# RJ45-2.net
KiCad netlist of a schematic drawn in Altium Designer
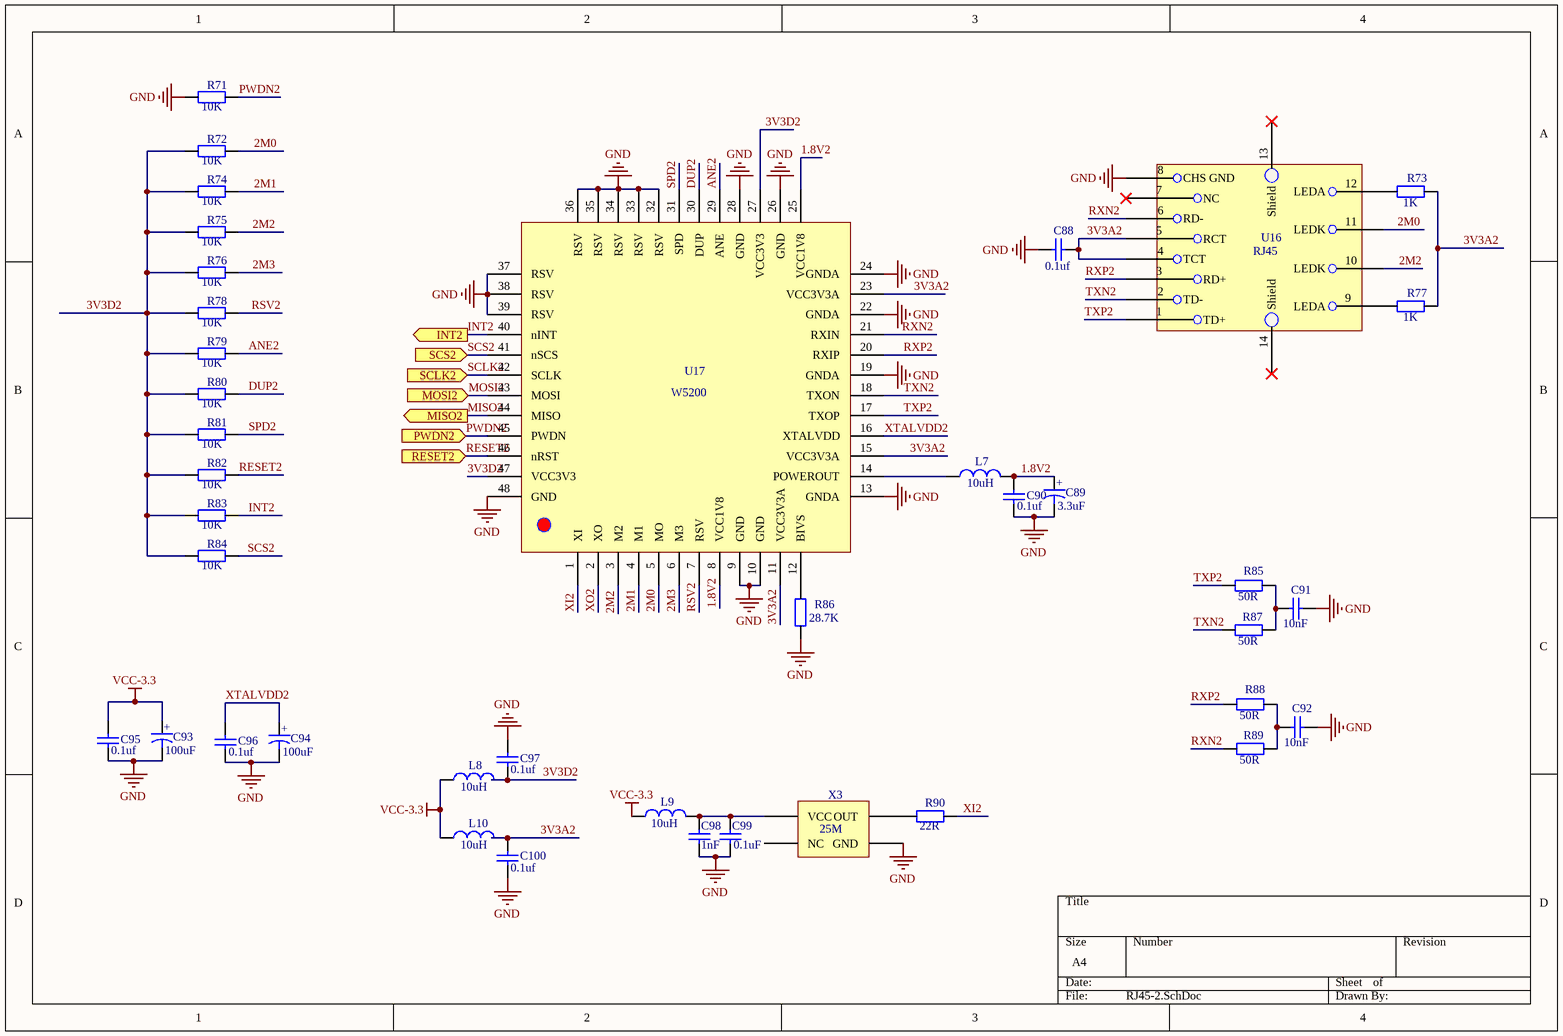
[diagram p0: RJ45-2.SchDoc]

(export (version "E")
  (design (tool "Eeschema 10.0.6"))
  (components
    (comp (ref "C88")
      (value "0.1uf")
      (footprint "0603")
      (fields (field (name "Comment") "Capacitor-0603"))
      (libsource (lib "原理图库") (part "Capacitor-0603"))
    )
    (comp (ref "C89")
      (value "3.3uF")
      (footprint "钽电容1206（A3216）")
      (fields (field (name "ALTIUM_UNNAMED_1") "+") (field (name "Comment") "电解电容"))
      (libsource (lib "原理图库") (part "电解电容"))
    )
    (comp (ref "C90")
      (value "0.1uf")
      (footprint "0603")
      (fields (field (name "Comment") "Capacitor-0603"))
      (libsource (lib "原理图库") (part "Capacitor-0603"))
    )
    (comp (ref "C91")
      (value "10nF")
      (footprint "0603")
      (fields (field (name "Comment") "Capacitor-0603"))
      (libsource (lib "原理图库") (part "Capacitor-0603"))
    )
    (comp (ref "C92")
      (value "10nF")
      (footprint "0603")
      (fields (field (name "Comment") "Capacitor-0603"))
      (libsource (lib "原理图库") (part "Capacitor-0603"))
    )
    (comp (ref "C93")
      (value "100uF")
      (footprint "钽电容1206（A3216）")
      (fields (field (name "ALTIUM_UNNAMED_1") "+") (field (name "Comment") "电解电容"))
      (libsource (lib "原理图库") (part "电解电容"))
    )
    (comp (ref "C94")
      (value "100uF")
      (footprint "钽电容1206（A3216）")
      (fields (field (name "ALTIUM_UNNAMED_1") "+") (field (name "Comment") "电解电容"))
      (libsource (lib "原理图库") (part "电解电容"))
    )
    (comp (ref "C95")
      (value "0.1uf")
      (footprint "0603")
      (fields (field (name "Comment") "Capacitor-0603"))
      (libsource (lib "原理图库") (part "Capacitor-0603"))
    )
    (comp (ref "C96")
      (value "0.1uf")
      (footprint "0603")
      (fields (field (name "Comment") "Capacitor-0603"))
      (libsource (lib "原理图库") (part "Capacitor-0603"))
    )
    (comp (ref "C97")
      (value "0.1uf")
      (footprint "0603")
      (fields (field (name "Comment") "Capacitor-0603"))
      (libsource (lib "原理图库") (part "Capacitor-0603"))
    )
    (comp (ref "C98")
      (value "1nF")
      (footprint "0603")
      (fields (field (name "Comment") "Capacitor-0603"))
      (libsource (lib "原理图库") (part "Capacitor-0603"))
    )
    (comp (ref "C99")
      (value "0.1uF")
      (footprint "0603")
      (fields (field (name "Comment") "Capacitor-0603"))
      (libsource (lib "原理图库") (part "Capacitor-0603"))
    )
    (comp (ref "C100")
      (value "0.1uf")
      (footprint "0603")
      (fields (field (name "Comment") "Capacitor-0603"))
      (libsource (lib "原理图库") (part "Capacitor-0603"))
    )
    (comp (ref "L7")
      (value "10uH")
      (footprint "0805")
      (fields (field (name "Comment") "Inductor"))
      (libsource (lib "原理图库") (part "Inductor"))
    )
    (comp (ref "L8")
      (value "10uH")
      (footprint "0805")
      (fields (field (name "Comment") "Inductor"))
      (libsource (lib "原理图库") (part "Inductor"))
    )
    (comp (ref "L9")
      (value "10uH")
      (footprint "0805")
      (fields (field (name "Comment") "Inductor"))
      (libsource (lib "原理图库") (part "Inductor"))
    )
    (comp (ref "L10")
      (value "10uH")
      (footprint "0805")
      (fields (field (name "Comment") "Inductor"))
      (libsource (lib "原理图库") (part "Inductor"))
    )
    (comp (ref "R71")
      (value "10K")
      (footprint "0603")
      (fields (field (name "Comment") "Resistor-0603"))
      (libsource (lib "原理图库") (part "Resistor-0603"))
    )
    (comp (ref "R72")
      (value "10K")
      (footprint "0603")
      (fields (field (name "Comment") "Resistor-0603"))
      (libsource (lib "原理图库") (part "Resistor-0603"))
    )
    (comp (ref "R73")
      (value "1K")
      (footprint "0603")
      (fields (field (name "Comment") "Resistor-0603"))
      (libsource (lib "原理图库") (part "Resistor-0603"))
    )
    (comp (ref "R74")
      (value "10K")
      (footprint "0603")
      (fields (field (name "Comment") "Resistor-0603"))
      (libsource (lib "原理图库") (part "Resistor-0603"))
    )
    (comp (ref "R75")
      (value "10K")
      (footprint "0603")
      (fields (field (name "Comment") "Resistor-0603"))
      (libsource (lib "原理图库") (part "Resistor-0603"))
    )
    (comp (ref "R76")
      (value "10K")
      (footprint "0603")
      (fields (field (name "Comment") "Resistor-0603"))
      (libsource (lib "原理图库") (part "Resistor-0603"))
    )
    (comp (ref "R77")
      (value "1K")
      (footprint "0603")
      (fields (field (name "Comment") "Resistor-0603"))
      (libsource (lib "原理图库") (part "Resistor-0603"))
    )
    (comp (ref "R78")
      (value "10K")
      (footprint "0603")
      (fields (field (name "Comment") "Resistor-0603"))
      (libsource (lib "原理图库") (part "Resistor-0603"))
    )
    (comp (ref "R79")
      (value "10K")
      (footprint "0603")
      (fields (field (name "Comment") "Resistor-0603"))
      (libsource (lib "原理图库") (part "Resistor-0603"))
    )
    (comp (ref "R80")
      (value "10K")
      (footprint "0603")
      (fields (field (name "Comment") "Resistor-0603"))
      (libsource (lib "原理图库") (part "Resistor-0603"))
    )
    (comp (ref "R81")
      (value "10K")
      (footprint "0603")
      (fields (field (name "Comment") "Resistor-0603"))
      (libsource (lib "原理图库") (part "Resistor-0603"))
    )
    (comp (ref "R82")
      (value "10K")
      (footprint "0603")
      (fields (field (name "Comment") "Resistor-0603"))
      (libsource (lib "原理图库") (part "Resistor-0603"))
    )
    (comp (ref "R83")
      (value "10K")
      (footprint "0603")
      (fields (field (name "Comment") "Resistor-0603"))
      (libsource (lib "原理图库") (part "Resistor-0603"))
    )
    (comp (ref "R84")
      (value "10K")
      (footprint "0603")
      (fields (field (name "Comment") "Resistor-0603"))
      (libsource (lib "原理图库") (part "Resistor-0603"))
    )
    (comp (ref "R85")
      (value "50R")
      (footprint "0603")
      (fields (field (name "Comment") "Resistor-0603"))
      (libsource (lib "原理图库") (part "Resistor-0603"))
    )
    (comp (ref "R86")
      (value "28.7K")
      (footprint "0603")
      (fields (field (name "Comment") "Resistor-0603"))
      (libsource (lib "") (part "Resistor-0603_1"))
    )
    (comp (ref "R87")
      (value "50R")
      (footprint "0603")
      (fields (field (name "Comment") "Resistor-0603"))
      (libsource (lib "原理图库") (part "Resistor-0603"))
    )
    (comp (ref "R88")
      (value "50R")
      (footprint "0603")
      (fields (field (name "Comment") "Resistor-0603"))
      (libsource (lib "原理图库") (part "Resistor-0603"))
    )
    (comp (ref "R89")
      (value "50R")
      (footprint "0603")
      (fields (field (name "Comment") "Resistor-0603"))
      (libsource (lib "原理图库") (part "Resistor-0603"))
    )
    (comp (ref "R90")
      (value "22R")
      (footprint "0603")
      (fields (field (name "Comment") "Resistor-0603"))
      (libsource (lib "原理图库") (part "Resistor-0603"))
    )
    (comp (ref "U16")
      (value "RJ45")
      (footprint "RJ45")
      (fields (field (name "NAME") "RJ45"))
      (libsource (lib "原理图库") (part "RJ45"))
    )
    (comp (ref "U17")
      (value "W5200-Chip")
      (footprint "W5200-Chip")
      (fields (field (name "NAME") "W5200"))
      (libsource (lib "原理图库") (part "W5200-Chip"))
    )
    (comp (ref "X3")
      (value "25M")
      (footprint "有源晶振7050")
      (fields (field (name "Comment") "有源晶振"))
      (libsource (lib "原理图库") (part "有源晶振"))
    )
  )
  (nets
    (net (code "1") (name "/1.8V2") (class "Default")
      (node (ref "C89") (pin "2") (pinfunction "2_2") (pintype "passive"))
      (node (ref "C90") (pin "2") (pinfunction "2_2") (pintype "passive"))
      (node (ref "L7") (pin "2") (pinfunction "2_2") (pintype "passive"))
      (node (ref "U17") (pin "25") (pinfunction "VCC1V8_25") (pintype "passive"))
      (node (ref "U17") (pin "8") (pinfunction "VCC1V8_8") (pintype "passive"))
    )
    (net (code "2") (name "/2M0") (class "Default")
      (node (ref "R72") (pin "2") (pinfunction "2_2") (pintype "passive"))
      (node (ref "U16") (pin "11") (pinfunction "LEDK_11") (pintype "passive"))
      (node (ref "U17") (pin "5") (pinfunction "MO_5") (pintype "passive"))
    )
    (net (code "3") (name "/2M1") (class "Default")
      (node (ref "R74") (pin "2") (pinfunction "2_2") (pintype "passive"))
      (node (ref "U17") (pin "4") (pinfunction "M1_4") (pintype "passive"))
    )
    (net (code "4") (name "/2M2") (class "Default")
      (node (ref "R75") (pin "2") (pinfunction "2_2") (pintype "passive"))
      (node (ref "U16") (pin "10") (pinfunction "LEDK_10") (pintype "passive"))
      (node (ref "U17") (pin "3") (pinfunction "M2_3") (pintype "passive"))
    )
    (net (code "5") (name "/2M3") (class "Default")
      (node (ref "R76") (pin "2") (pinfunction "2_2") (pintype "passive"))
      (node (ref "U17") (pin "6") (pinfunction "M3_6") (pintype "passive"))
    )
    (net (code "6") (name "/3V3A2") (class "Default")
      (node (ref "C100") (pin "1") (pinfunction "1_1") (pintype "passive"))
      (node (ref "C88") (pin "1") (pinfunction "1_1") (pintype "passive"))
      (node (ref "L10") (pin "2") (pinfunction "2_2") (pintype "passive"))
      (node (ref "R73") (pin "2") (pinfunction "2_2") (pintype "passive"))
      (node (ref "R77") (pin "2") (pinfunction "2_2") (pintype "passive"))
      (node (ref "U16") (pin "4") (pinfunction "TCT_4") (pintype "passive"))
      (node (ref "U16") (pin "5") (pinfunction "RCT_5") (pintype "passive"))
      (node (ref "U17") (pin "11") (pinfunction "VCC3V3A_11") (pintype "passive"))
      (node (ref "U17") (pin "15") (pinfunction "VCC3V3A_15") (pintype "passive"))
      (node (ref "U17") (pin "23") (pinfunction "VCC3V3A_23") (pintype "passive"))
    )
    (net (code "7") (name "/3V3D2") (class "Default")
      (node (ref "C97") (pin "1") (pinfunction "1_1") (pintype "passive"))
      (node (ref "L8") (pin "2") (pinfunction "2_2") (pintype "passive"))
      (node (ref "R72") (pin "1") (pinfunction "1_1") (pintype "passive"))
      (node (ref "R74") (pin "1") (pinfunction "1_1") (pintype "passive"))
      (node (ref "R75") (pin "1") (pinfunction "1_1") (pintype "passive"))
      (node (ref "R76") (pin "1") (pinfunction "1_1") (pintype "passive"))
      (node (ref "R78") (pin "1") (pinfunction "1_1") (pintype "passive"))
      (node (ref "R79") (pin "1") (pinfunction "1_1") (pintype "passive"))
      (node (ref "R80") (pin "1") (pinfunction "1_1") (pintype "passive"))
      (node (ref "R81") (pin "1") (pinfunction "1_1") (pintype "passive"))
      (node (ref "R82") (pin "1") (pinfunction "1_1") (pintype "passive"))
      (node (ref "R83") (pin "1") (pinfunction "1_1") (pintype "passive"))
      (node (ref "R84") (pin "1") (pinfunction "1_1") (pintype "passive"))
      (node (ref "U17") (pin "27") (pinfunction "VCC3V3_27") (pintype "passive"))
      (node (ref "U17") (pin "47") (pinfunction "VCC3V3_47") (pintype "passive"))
    )
    (net (code "8") (name "/ANE2") (class "Default")
      (node (ref "R79") (pin "2") (pinfunction "2_2") (pintype "passive"))
      (node (ref "U17") (pin "29") (pinfunction "ANE_29") (pintype "passive"))
    )
    (net (code "9") (name "/DUP2") (class "Default")
      (node (ref "R80") (pin "2") (pinfunction "2_2") (pintype "passive"))
      (node (ref "U17") (pin "30") (pinfunction "DUP_30") (pintype "passive"))
    )
    (net (code "10") (name "/INT2") (class "Default")
      (node (ref "R83") (pin "2") (pinfunction "2_2") (pintype "passive"))
      (node (ref "U17") (pin "40") (pinfunction "nINT_40") (pintype "passive"))
    )
    (net (code "11") (name "/MISO2") (class "Default")
      (node (ref "U17") (pin "44") (pinfunction "MISO_44") (pintype "passive"))
    )
    (net (code "12") (name "/MOSI2") (class "Default")
      (node (ref "U17") (pin "43") (pinfunction "MOSI_43") (pintype "passive"))
    )
    (net (code "13") (name "/PWDN2") (class "Default")
      (node (ref "R71") (pin "2") (pinfunction "2_2") (pintype "passive"))
      (node (ref "U17") (pin "45") (pinfunction "PWDN_45") (pintype "passive"))
    )
    (net (code "14") (name "/RESET2") (class "Default")
      (node (ref "R82") (pin "2") (pinfunction "2_2") (pintype "passive"))
      (node (ref "U17") (pin "46") (pinfunction "nRST_46") (pintype "passive"))
    )
    (net (code "15") (name "/RSV2") (class "Default")
      (node (ref "R78") (pin "2") (pinfunction "2_2") (pintype "passive"))
      (node (ref "U17") (pin "7") (pinfunction "RSV_7") (pintype "passive"))
    )
    (net (code "16") (name "/RXN2") (class "Default")
      (node (ref "R89") (pin "1") (pinfunction "1_1") (pintype "passive"))
      (node (ref "U16") (pin "6") (pinfunction "RD-_6") (pintype "passive"))
      (node (ref "U17") (pin "21") (pinfunction "RXIN_21") (pintype "passive"))
    )
    (net (code "17") (name "/RXP2") (class "Default")
      (node (ref "R88") (pin "1") (pinfunction "1_1") (pintype "passive"))
      (node (ref "U16") (pin "3") (pinfunction "RD+_3") (pintype "passive"))
      (node (ref "U17") (pin "20") (pinfunction "RXIP_20") (pintype "passive"))
    )
    (net (code "18") (name "/SCLK2") (class "Default")
      (node (ref "U17") (pin "42") (pinfunction "SCLK_42") (pintype "passive"))
    )
    (net (code "19") (name "/SCS2") (class "Default")
      (node (ref "R84") (pin "2") (pinfunction "2_2") (pintype "passive"))
      (node (ref "U17") (pin "41") (pinfunction "nSCS_41") (pintype "passive"))
    )
    (net (code "20") (name "/SPD2") (class "Default")
      (node (ref "R81") (pin "2") (pinfunction "2_2") (pintype "passive"))
      (node (ref "U17") (pin "31") (pinfunction "SPD_31") (pintype "passive"))
    )
    (net (code "21") (name "/TXN2") (class "Default")
      (node (ref "R87") (pin "1") (pinfunction "1_1") (pintype "passive"))
      (node (ref "U16") (pin "2") (pinfunction "TD-_2") (pintype "passive"))
      (node (ref "U17") (pin "18") (pinfunction "TXON_18") (pintype "passive"))
    )
    (net (code "22") (name "/TXP2") (class "Default")
      (node (ref "R85") (pin "1") (pinfunction "1_1") (pintype "passive"))
      (node (ref "U16") (pin "1") (pinfunction "TD+_1") (pintype "passive"))
      (node (ref "U17") (pin "17") (pinfunction "TXOP_17") (pintype "passive"))
    )
    (net (code "23") (name "/XI2") (class "Default")
      (node (ref "R90") (pin "2") (pinfunction "2_2") (pintype "passive"))
      (node (ref "U17") (pin "1") (pinfunction "XI_1") (pintype "passive"))
    )
    (net (code "24") (name "/XO2") (class "Default")
      (node (ref "U17") (pin "2") (pinfunction "XO_2") (pintype "passive"))
    )
    (net (code "25") (name "/XTALVDD2") (class "Default")
      (node (ref "C94") (pin "2") (pinfunction "2_2") (pintype "passive"))
      (node (ref "C96") (pin "2") (pinfunction "2_2") (pintype "passive"))
      (node (ref "U17") (pin "16") (pinfunction "XTALVDD_16") (pintype "passive"))
    )
    (net (code "26") (name "GND") (class "Default")
      (node (ref "C100") (pin "2") (pinfunction "2_2") (pintype "passive"))
      (node (ref "C88") (pin "2") (pinfunction "2_2") (pintype "passive"))
      (node (ref "C89") (pin "1") (pinfunction "1_1") (pintype "passive"))
      (node (ref "C90") (pin "1") (pinfunction "1_1") (pintype "passive"))
      (node (ref "C91") (pin "2") (pinfunction "2_2") (pintype "passive"))
      (node (ref "C92") (pin "2") (pinfunction "2_2") (pintype "passive"))
      (node (ref "C93") (pin "1") (pinfunction "1_1") (pintype "passive"))
      (node (ref "C94") (pin "1") (pinfunction "1_1") (pintype "passive"))
      (node (ref "C95") (pin "1") (pinfunction "1_1") (pintype "passive"))
      (node (ref "C96") (pin "1") (pinfunction "1_1") (pintype "passive"))
      (node (ref "C97") (pin "2") (pinfunction "2_2") (pintype "passive"))
      (node (ref "C98") (pin "2") (pinfunction "2_2") (pintype "passive"))
      (node (ref "C99") (pin "2") (pinfunction "2_2") (pintype "passive"))
      (node (ref "R71") (pin "1") (pinfunction "1_1") (pintype "passive"))
      (node (ref "R86") (pin "1") (pinfunction "1_1") (pintype "passive"))
      (node (ref "U16") (pin "8") (pinfunction "CHS_GND_8") (pintype "passive"))
      (node (ref "U17") (pin "10") (pinfunction "GND_10") (pintype "passive"))
      (node (ref "U17") (pin "13") (pinfunction "GNDA_13") (pintype "passive"))
      (node (ref "U17") (pin "19") (pinfunction "GNDA_19") (pintype "passive"))
      (node (ref "U17") (pin "22") (pinfunction "GNDA_22") (pintype "passive"))
      (node (ref "U17") (pin "24") (pinfunction "GNDA_24") (pintype "passive"))
      (node (ref "U17") (pin "26") (pinfunction "GND_26") (pintype "passive"))
      (node (ref "U17") (pin "28") (pinfunction "GND_28") (pintype "passive"))
      (node (ref "U17") (pin "32") (pinfunction "RSV_32") (pintype "passive"))
      (node (ref "U17") (pin "33") (pinfunction "RSV_33") (pintype "passive"))
      (node (ref "U17") (pin "34") (pinfunction "RSV_34") (pintype "passive"))
      (node (ref "U17") (pin "35") (pinfunction "RSV_35") (pintype "passive"))
      (node (ref "U17") (pin "36") (pinfunction "RSV_36") (pintype "passive"))
      (node (ref "U17") (pin "37") (pinfunction "RSV_37") (pintype "passive"))
      (node (ref "U17") (pin "38") (pinfunction "RSV_38") (pintype "passive"))
      (node (ref "U17") (pin "39") (pinfunction "RSV_39") (pintype "passive"))
      (node (ref "U17") (pin "48") (pinfunction "GND_48") (pintype "passive"))
      (node (ref "U17") (pin "9") (pinfunction "GND_9") (pintype "passive"))
      (node (ref "X3") (pin "2") (pinfunction "GND_2") (pintype "passive"))
    )
    (net (code "27") (name "Net-(C91-Pad1)") (class "Default")
      (node (ref "C91") (pin "1") (pinfunction "1_1") (pintype "passive"))
      (node (ref "R85") (pin "2") (pinfunction "2_2") (pintype "passive"))
      (node (ref "R87") (pin "2") (pinfunction "2_2") (pintype "passive"))
    )
    (net (code "28") (name "Net-(C92-Pad1)") (class "Default")
      (node (ref "C92") (pin "1") (pinfunction "1_1") (pintype "passive"))
      (node (ref "R88") (pin "2") (pinfunction "2_2") (pintype "passive"))
      (node (ref "R89") (pin "2") (pinfunction "2_2") (pintype "passive"))
    )
    (net (code "29") (name "Net-(R73-Pad1)") (class "Default")
      (node (ref "R73") (pin "1") (pinfunction "1_1") (pintype "passive"))
      (node (ref "U16") (pin "12") (pinfunction "LEDA_12") (pintype "passive"))
    )
    (net (code "30") (name "Net-(R77-Pad1)") (class "Default")
      (node (ref "R77") (pin "1") (pinfunction "1_1") (pintype "passive"))
      (node (ref "U16") (pin "9") (pinfunction "LEDA_9") (pintype "passive"))
    )
    (net (code "31") (name "Net-(U17-BIVS)") (class "Default")
      (node (ref "R86") (pin "2") (pinfunction "2_2") (pintype "passive"))
      (node (ref "U17") (pin "12") (pinfunction "BIVS_12") (pintype "passive"))
    )
    (net (code "32") (name "Net-(U17-POWEROUT)") (class "Default")
      (node (ref "L7") (pin "1") (pinfunction "1_1") (pintype "passive"))
      (node (ref "U17") (pin "14") (pinfunction "POWEROUT_14") (pintype "passive"))
    )
    (net (code "33") (name "Net-(X3-OUT)") (class "Default")
      (node (ref "R90") (pin "1") (pinfunction "1_1") (pintype "passive"))
      (node (ref "X3") (pin "3") (pinfunction "OUT_3") (pintype "passive"))
    )
    (net (code "34") (name "Net-(X3-VCC)") (class "Default")
      (node (ref "C98") (pin "1") (pinfunction "1_1") (pintype "passive"))
      (node (ref "C99") (pin "1") (pinfunction "1_1") (pintype "passive"))
      (node (ref "L9") (pin "2") (pinfunction "2_2") (pintype "passive"))
      (node (ref "X3") (pin "4") (pinfunction "VCC_4") (pintype "passive"))
    )
    (net (code "35") (name "VCC-3.3") (class "Default")
      (node (ref "C93") (pin "2") (pinfunction "2_2") (pintype "passive"))
      (node (ref "C95") (pin "2") (pinfunction "2_2") (pintype "passive"))
      (node (ref "L10") (pin "1") (pinfunction "1_1") (pintype "passive"))
      (node (ref "L8") (pin "1") (pinfunction "1_1") (pintype "passive"))
      (node (ref "L9") (pin "1") (pinfunction "1_1") (pintype "passive"))
    )
    (net (code "36") (name "unconnected-(U16-NC-Pad7)") (class "Default")
      (node (ref "U16") (pin "7") (pinfunction "NC_7") (pintype "passive+no_connect"))
    )
    (net (code "37") (name "unconnected-(U16-Shield-Pad13)") (class "Default")
      (node (ref "U16") (pin "13") (pinfunction "Shield_13") (pintype "passive+no_connect"))
    )
    (net (code "38") (name "unconnected-(U16-Shield-Pad14)") (class "Default")
      (node (ref "U16") (pin "14") (pinfunction "Shield_14") (pintype "passive+no_connect"))
    )
    (net (code "39") (name "unconnected-(X3-NC-Pad1)") (class "Default")
      (node (ref "X3") (pin "1") (pinfunction "NC_1") (pintype "passive"))
    )
  )
)
